# KMO_IO_MV2_8_min.net
KiCad netlist of a schematic drawn in EAGLE
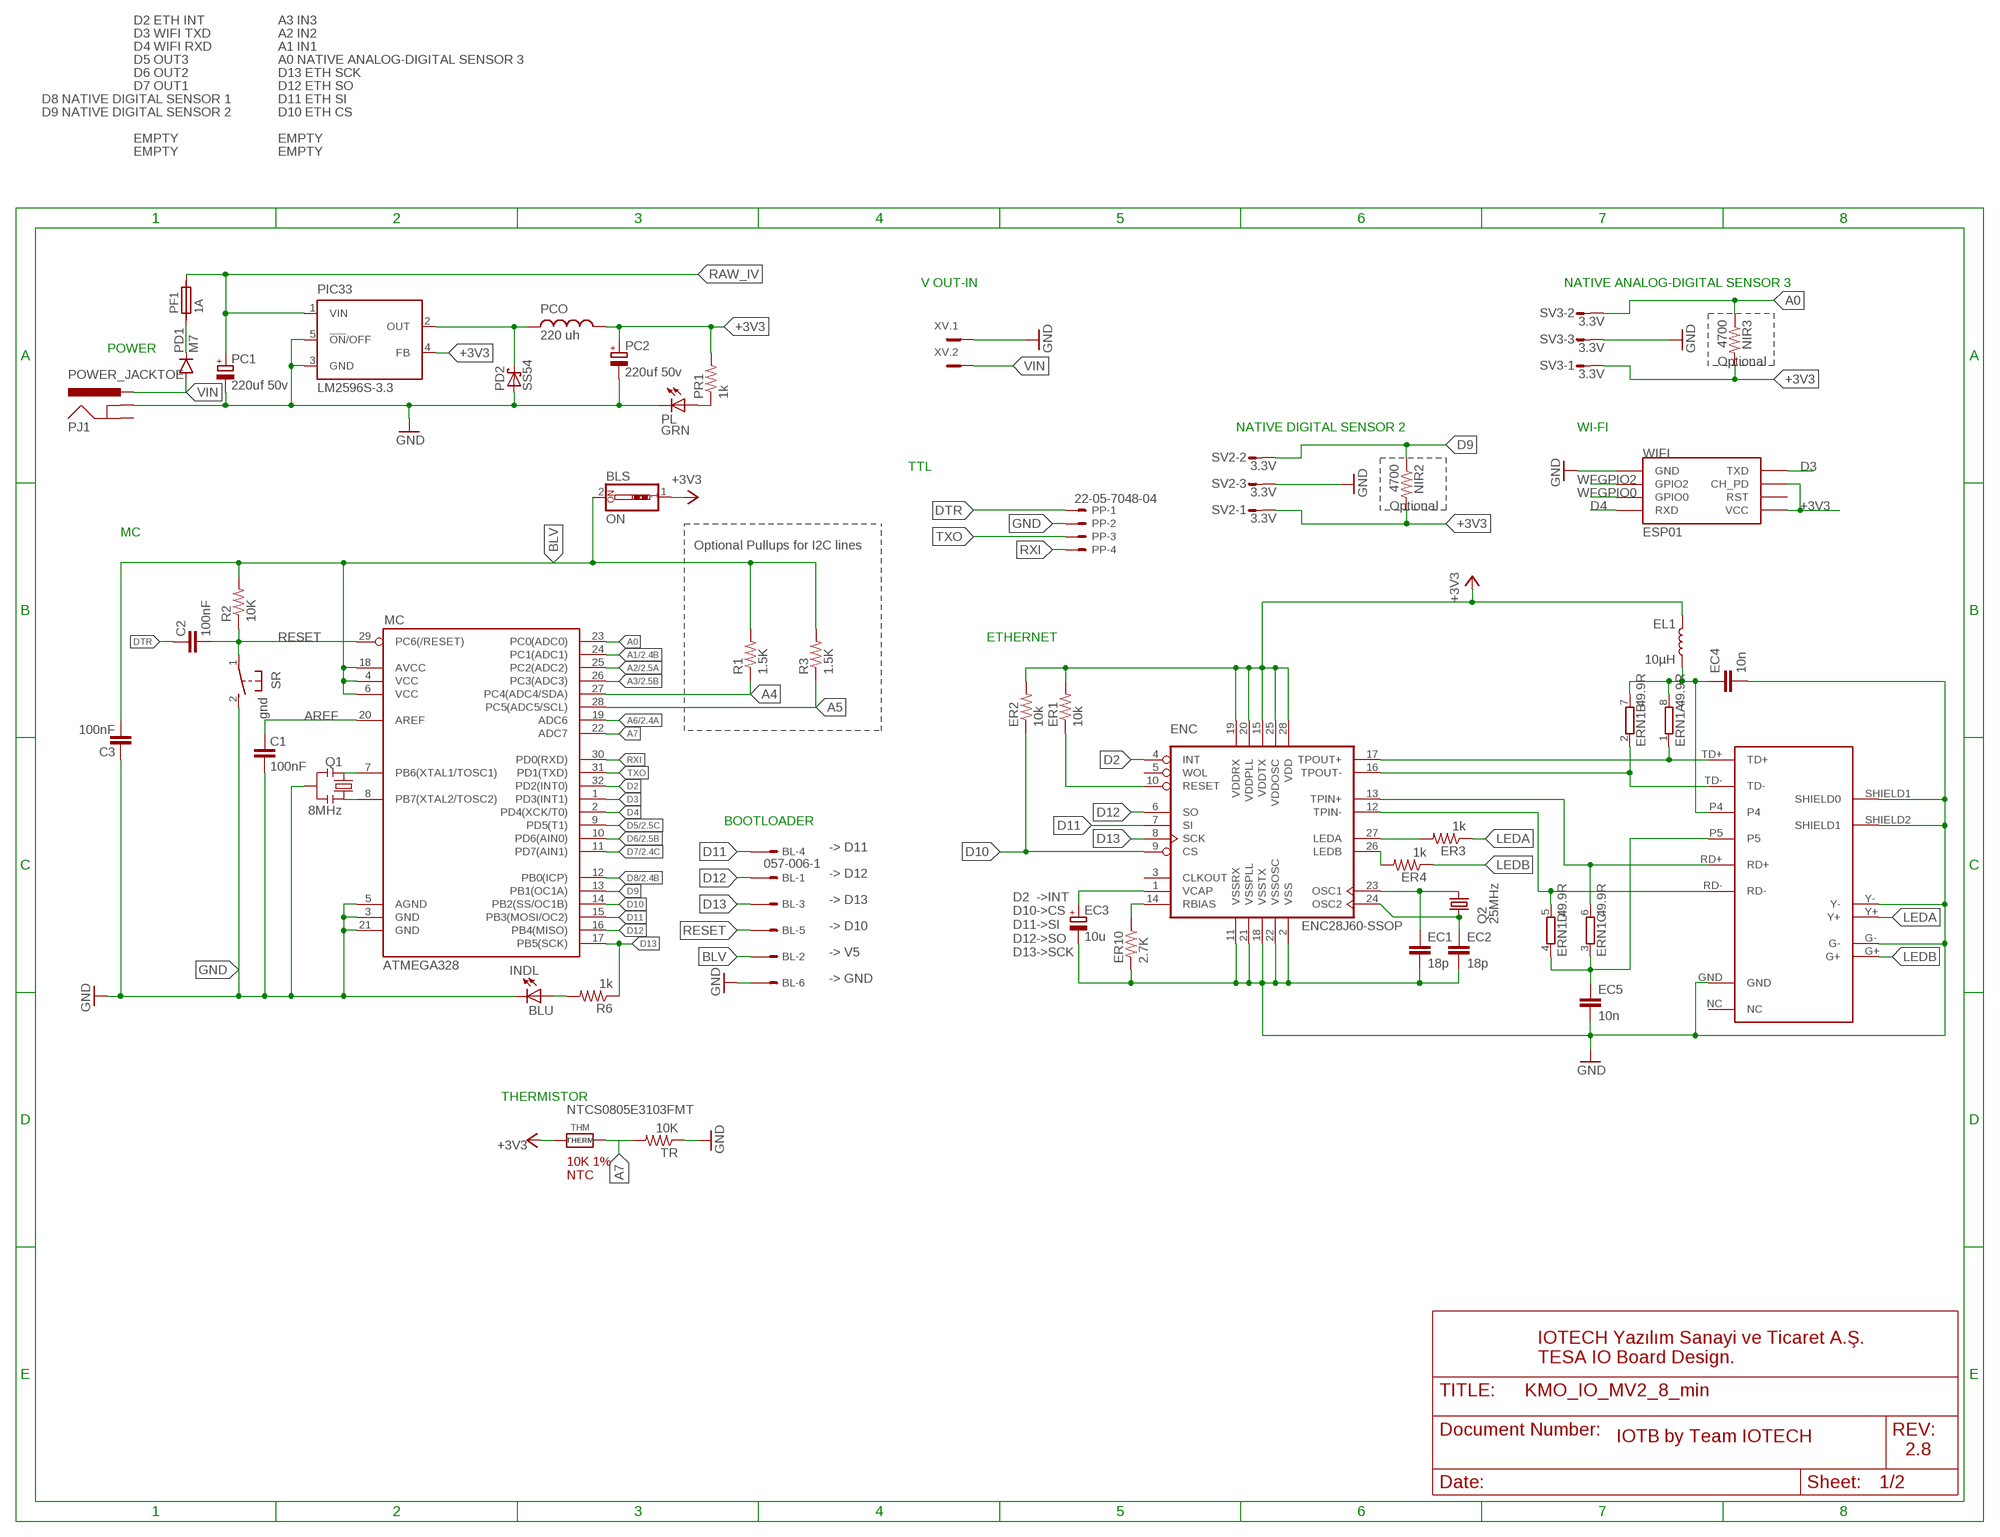
[diagram p0: schematic, sheet 1]
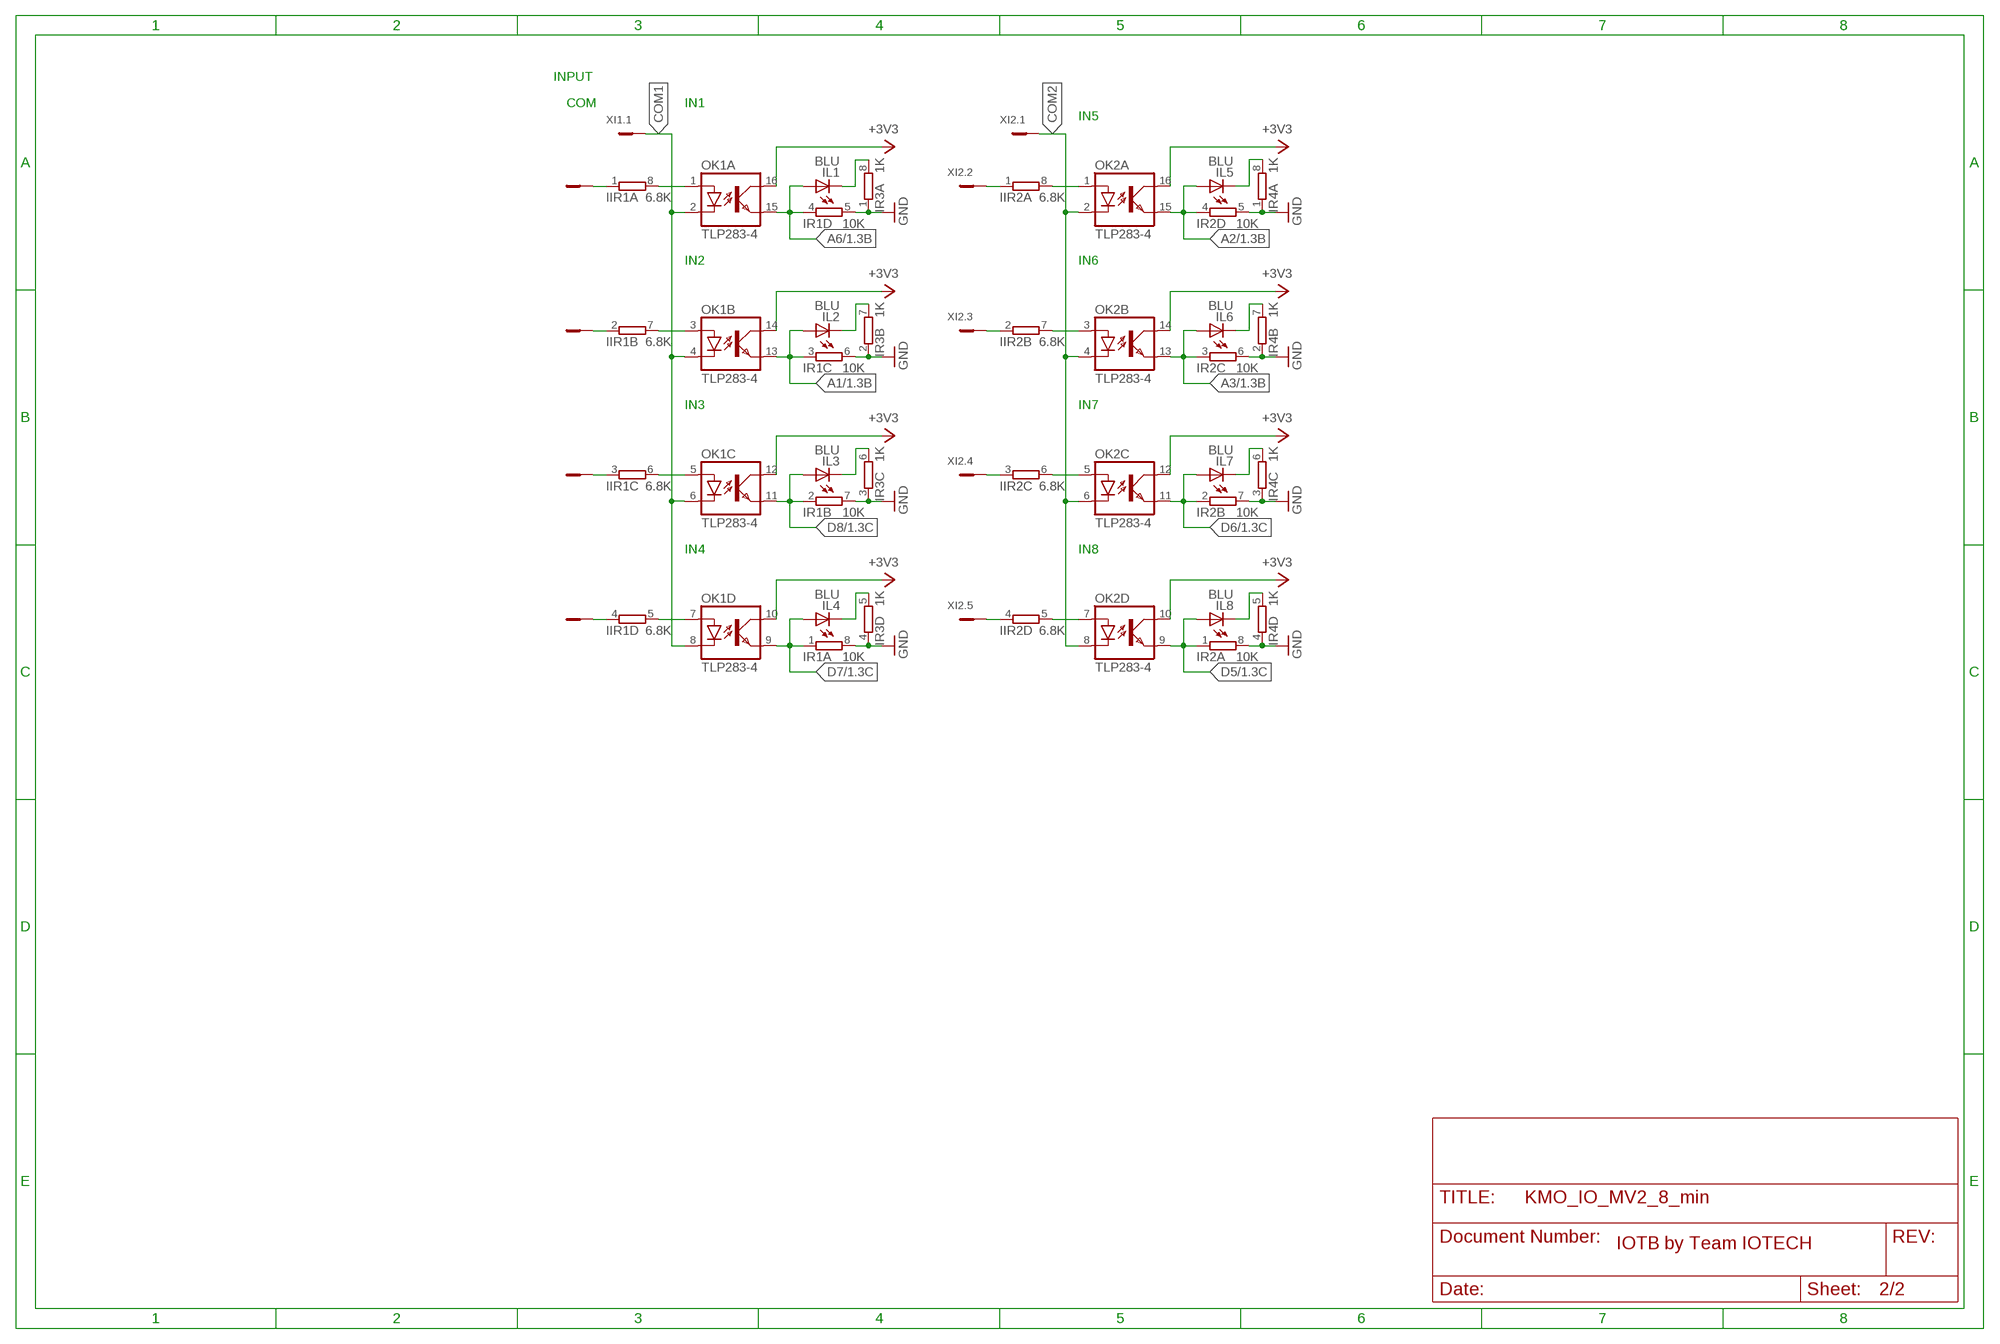
[diagram p1: schematic, sheet 2]

(export (version "E")
  (design (tool "Eeschema 10.0.6"))
  (components
    (comp (ref "IIR1")
      (value "6.8K")
      (footprint "eagle-import:0603-ARV")
      (libsource (lib "eagle-import") (part "4R-N0603-ARV"))
    )
    (comp (ref "IIR2")
      (value "6.8K")
      (footprint "eagle-import:0603-ARV")
      (libsource (lib "eagle-import") (part "4R-N0603-ARV"))
    )
    (comp (ref "IL1")
      (value "BLU")
      (footprint "eagle-import:CHIP-LED0805")
      (libsource (lib "eagle-import") (part "LEDCHIP-LED0805"))
    )
    (comp (ref "IL2")
      (value "BLU")
      (footprint "eagle-import:CHIP-LED0805")
      (libsource (lib "eagle-import") (part "LEDCHIP-LED0805"))
    )
    (comp (ref "IL3")
      (value "BLU")
      (footprint "eagle-import:CHIP-LED0805")
      (libsource (lib "eagle-import") (part "LEDCHIP-LED0805"))
    )
    (comp (ref "IL4")
      (value "BLU")
      (footprint "eagle-import:CHIP-LED0805")
      (libsource (lib "eagle-import") (part "LEDCHIP-LED0805"))
    )
    (comp (ref "IL5")
      (value "BLU")
      (footprint "eagle-import:CHIP-LED0805")
      (libsource (lib "eagle-import") (part "LEDCHIP-LED0805"))
    )
    (comp (ref "IL6")
      (value "BLU")
      (footprint "eagle-import:CHIP-LED0805")
      (libsource (lib "eagle-import") (part "LEDCHIP-LED0805"))
    )
    (comp (ref "IL7")
      (value "BLU")
      (footprint "eagle-import:CHIP-LED0805")
      (libsource (lib "eagle-import") (part "LEDCHIP-LED0805"))
    )
    (comp (ref "IL8")
      (value "BLU")
      (footprint "eagle-import:CHIP-LED0805")
      (libsource (lib "eagle-import") (part "LEDCHIP-LED0805"))
    )
    (comp (ref "IR1")
      (value "10K")
      (footprint "eagle-import:0603-ARV")
      (libsource (lib "eagle-import") (part "4R-N0603-ARV"))
    )
    (comp (ref "IR2")
      (value "10K")
      (footprint "eagle-import:0603-ARV")
      (libsource (lib "eagle-import") (part "4R-N0603-ARV"))
    )
    (comp (ref "IR3")
      (value "1K")
      (footprint "eagle-import:0603-ARV")
      (libsource (lib "eagle-import") (part "4R-N0603-ARV"))
    )
    (comp (ref "IR4")
      (value "1K")
      (footprint "eagle-import:0603-ARV")
      (libsource (lib "eagle-import") (part "4R-N0603-ARV"))
    )
    (comp (ref "OK1")
      (value "TLP283-4")
      (footprint "eagle-import:MINI-FLAT-16")
      (fields (field (name "SPICEPREFIX") "O"))
      (libsource (lib "eagle-import") (part "TLP283-4"))
    )
    (comp (ref "OK2")
      (value "TLP283-4")
      (footprint "eagle-import:MINI-FLAT-16")
      (fields (field (name "SPICEPREFIX") "O"))
      (libsource (lib "eagle-import") (part "TLP283-4"))
    )
    (comp (ref "XI1")
      (value "MC5")
      (footprint "eagle-import:MC5")
      (libsource (lib "eagle-import") (part "MC5"))
    )
    (comp (ref "XI2")
      (value "MC5")
      (footprint "eagle-import:MC5")
      (libsource (lib "eagle-import") (part "MC5"))
    )
    (comp (ref "BL")
      (value "057-006-1")
      (footprint "eagle-import:057-006-1")
      (libsource (lib "eagle-import") (part "057-006-1"))
    )
    (comp (ref "BLS")
      (value "ON")
      (footprint "eagle-import:EDG-01")
      (libsource (lib "eagle-import") (part "SW_DIP-1"))
    )
    (comp (ref "C1")
      (value "100nF")
      (footprint "eagle-import:0805")
      (libsource (lib "eagle-import") (part "CAP0805"))
    )
    (comp (ref "C2")
      (value "100nF")
      (footprint "eagle-import:0805")
      (libsource (lib "eagle-import") (part "CAP0805"))
    )
    (comp (ref "C3")
      (value "100nF")
      (footprint "eagle-import:0805")
      (libsource (lib "eagle-import") (part "CAP0805"))
    )
    (comp (ref "EC1")
      (value "18p")
      (footprint "eagle-import:0805")
      (libsource (lib "eagle-import") (part "CAP0805"))
    )
    (comp (ref "EC2")
      (value "18p")
      (footprint "eagle-import:0805")
      (libsource (lib "eagle-import") (part "CAP0805"))
    )
    (comp (ref "EC3")
      (value "10u")
      (footprint "eagle-import:CT3216")
      (libsource (lib "eagle-import") (part "CPOL-EUCT3216"))
    )
    (comp (ref "EC4")
      (value "10n")
      (footprint "eagle-import:0805")
      (libsource (lib "eagle-import") (part "CAP0805"))
    )
    (comp (ref "EC5")
      (value "10n")
      (footprint "eagle-import:0805")
      (libsource (lib "eagle-import") (part "CAP0805"))
    )
    (comp (ref "EL1")
      (value "10µH")
      (footprint "eagle-import:0805")
      (libsource (lib "eagle-import") (part "INDUCTOR-0805-3.3UH"))
    )
    (comp (ref "ENC")
      (value "ENC28J60-SSOP")
      (footprint "eagle-import:SSOP28")
      (libsource (lib "eagle-import") (part "ENC28J60-SSOP"))
    )
    (comp (ref "ER1")
      (value "10k")
      (footprint "eagle-import:0805")
      (libsource (lib "eagle-import") (part "RESISTOR0805-RES"))
    )
    (comp (ref "ER2")
      (value "10k")
      (footprint "eagle-import:0805")
      (libsource (lib "eagle-import") (part "RESISTOR0805-RES"))
    )
    (comp (ref "ER3")
      (value "1k")
      (footprint "eagle-import:0805")
      (libsource (lib "eagle-import") (part "RESISTOR0805-RES"))
    )
    (comp (ref "ER4")
      (value "1k")
      (footprint "eagle-import:0805")
      (libsource (lib "eagle-import") (part "RESISTOR0805-RES"))
    )
    (comp (ref "ER10")
      (value "2.7K")
      (footprint "eagle-import:0805")
      (libsource (lib "eagle-import") (part "RESISTOR0805-RES"))
    )
    (comp (ref "ERN1")
      (value "49.9R")
      (footprint "eagle-import:0603-ARV")
      (libsource (lib "eagle-import") (part "4R-N0603-ARV"))
    )
    (comp (ref "INDL")
      (value "BLU")
      (footprint "eagle-import:CHIP-LED0805")
      (libsource (lib "eagle-import") (part "LEDCHIP-LED0805"))
    )
    (comp (ref "MC")
      (value "ATMEGA328")
      (footprint "eagle-import:TQFP32-08")
      (libsource (lib "eagle-import") (part "ATMEGA168"))
    )
    (comp (ref "NIR2")
      (value "4700")
      (footprint "eagle-import:0805")
      (libsource (lib "eagle-import") (part "RESISTOR0805-RES"))
    )
    (comp (ref "NIR3")
      (value "4700")
      (footprint "eagle-import:0805")
      (libsource (lib "eagle-import") (part "RESISTOR0805-RES"))
    )
    (comp (ref "PC1")
      (value "220uf 50v")
      (footprint "eagle-import:140CLH-1010")
      (libsource (lib "eagle-import") (part "CPOL-EU140CLH-1010"))
    )
    (comp (ref "PC2")
      (value "220uf 50v")
      (footprint "eagle-import:140CLH-1010")
      (libsource (lib "eagle-import") (part "CPOL-EU140CLH-1010"))
    )
    (comp (ref "PCO")
      (value "220 uh")
      (footprint "eagle-import:MSS1260")
      (libsource (lib "eagle-import") (part "MSS1260"))
    )
    (comp (ref "PD1")
      (value "M7")
      (footprint "eagle-import:SMA-DIODE")
      (libsource (lib "eagle-import") (part "DIODESMA"))
    )
    (comp (ref "PD2")
      (value "SS54")
      (footprint "eagle-import:SMB")
      (libsource (lib "eagle-import") (part "SCHOTTKY-DIODESMD"))
    )
    (comp (ref "PF1")
      (value "1A")
      (footprint "eagle-import:1820")
      (libsource (lib "eagle-import") (part "SIBA194600"))
    )
    (comp (ref "PIC33")
      (value "LM2596S-3.3")
      (footprint "eagle-import:TO263-5")
      (fields
        (field (name "MF") "NATIONAL SEMICONDUCTOR")
        (field (name "MPN") "LM2596S-ADJ/NOPB")
        (field (name "SPICEPREFIX") "X")
      )
      (libsource (lib "eagle-import") (part "LM2596S"))
    )
    (comp (ref "PJ1")
      (value "POWER_JACKTOE")
      (footprint "eagle-import:POWER_JACK_SMD_OVERPASTE_TOE")
      (libsource (lib "eagle-import") (part "POWER_JACKTOE"))
    )
    (comp (ref "PL")
      (value "GRN")
      (footprint "eagle-import:CHIP-LED0805")
      (libsource (lib "eagle-import") (part "LEDCHIP-LED0805"))
    )
    (comp (ref "PP")
      (value "22-05-7048-04")
      (footprint "eagle-import:7395-04")
      (fields (field (name "MF") "MOLEX"))
      (libsource (lib "eagle-import") (part "22-?-0405-7048"))
    )
    (comp (ref "PR1")
      (value "1k")
      (footprint "eagle-import:0805")
      (libsource (lib "eagle-import") (part "RESISTOR0805-RES"))
    )
    (comp (ref "Q1")
      (value "8MHz")
      (footprint "eagle-import:RESONATOR-SMD-1_1")
      (libsource (lib "eagle-import") (part "RESONATOR1{colon}1"))
    )
    (comp (ref "Q2")
      (value "25MHz")
      (footprint "eagle-import:5.0X3.2_2")
      (libsource (lib "eagle-import") (part "KX-9B"))
    )
    (comp (ref "R1")
      (value "1.5K")
      (footprint "eagle-import:0805")
      (libsource (lib "eagle-import") (part "RESISTOR0805-RES"))
    )
    (comp (ref "R2")
      (value "10K")
      (footprint "eagle-import:0805")
      (libsource (lib "eagle-import") (part "RESISTOR0805-RES"))
    )
    (comp (ref "R3")
      (value "1.5K")
      (footprint "eagle-import:0805")
      (libsource (lib "eagle-import") (part "RESISTOR0805-RES"))
    )
    (comp (ref "R6")
      (value "1k")
      (footprint "eagle-import:0805")
      (libsource (lib "eagle-import") (part "RESISTOR0805-RES"))
    )
    (comp (ref "SR")
      (value "gnd")
      (footprint "eagle-import:B3F-31XX")
      (fields (field (name "MPN") "B3F-3100"))
      (libsource (lib "eagle-import") (part "31-XX"))
    )
    (comp (ref "SV2")
      (value "3.3V")
      (footprint "eagle-import:S03P")
      (libsource (lib "eagle-import") (part "S03P"))
    )
    (comp (ref "SV3")
      (value "3.3V")
      (footprint "eagle-import:S03P")
      (libsource (lib "eagle-import") (part "S03P"))
    )
    (comp (ref "THM")
      (value "THERM")
      (footprint "eagle-import:MICROBUILDER_0805_NOTHERMALS")
      (libsource (lib "eagle-import") (part "MICROBUILDER_RESISTOR0805_NOTHERMALS"))
    )
    (comp (ref "TR")
      (value "10K")
      (footprint "eagle-import:0805")
      (libsource (lib "eagle-import") (part "RESISTOR0805-RES"))
    )
    (comp (ref "U$2")
      (value "HR911105A")
      (footprint "eagle-import:RJ45")
      (libsource (lib "eagle-import") (part "HR911105A"))
    )
    (comp (ref "WIFI")
      (value "ESP01")
      (footprint "eagle-import:ESP01")
      (libsource (lib "eagle-import") (part "ESP01"))
    )
    (comp (ref "XV")
      (value "MC2")
      (footprint "eagle-import:MC2")
      (libsource (lib "eagle-import") (part "MC2"))
    )
  )
  (nets
    (net (code "1") (name "+3V3") (class "Default")
      (node (ref "BLS") (pin "1") (pinfunction "1_1") (pintype "passive"))
      (node (ref "EL1") (pin "1") (pinfunction "1_1") (pintype "passive"))
      (node (ref "ENC") (pin "15") (pinfunction "VDDTX_15") (pintype "power_in"))
      (node (ref "ENC") (pin "19") (pinfunction "VDDRX_19") (pintype "power_in"))
      (node (ref "ENC") (pin "20") (pinfunction "VDDPLL_20") (pintype "power_in"))
      (node (ref "ENC") (pin "25") (pinfunction "VDDOSC_25") (pintype "power_in"))
      (node (ref "ENC") (pin "28") (pinfunction "VDD_28") (pintype "power_in"))
      (node (ref "ER1") (pin "2") (pinfunction "2_2") (pintype "passive"))
      (node (ref "ER2") (pin "2") (pinfunction "2_2") (pintype "passive"))
      (node (ref "NIR2") (pin "2") (pinfunction "2_2") (pintype "passive"))
      (node (ref "NIR3") (pin "2") (pinfunction "2_2") (pintype "passive"))
      (node (ref "OK1") (pin "10") (pinfunction "COL_10") (pintype "passive"))
      (node (ref "OK1") (pin "12") (pinfunction "COL_12") (pintype "passive"))
      (node (ref "OK1") (pin "14") (pinfunction "COL_14") (pintype "passive"))
      (node (ref "OK1") (pin "16") (pinfunction "COL_16") (pintype "passive"))
      (node (ref "OK2") (pin "10") (pinfunction "COL_10") (pintype "passive"))
      (node (ref "OK2") (pin "12") (pinfunction "COL_12") (pintype "passive"))
      (node (ref "OK2") (pin "14") (pinfunction "COL_14") (pintype "passive"))
      (node (ref "OK2") (pin "16") (pinfunction "COL_16") (pintype "passive"))
      (node (ref "PC2") (pin "+") (pinfunction "+_+") (pintype "passive"))
      (node (ref "PCO") (pin "P$1") (pinfunction "P$1_P$1") (pintype "passive"))
      (node (ref "PIC33") (pin "4") (pinfunction "FB_4") (pintype "input"))
      (node (ref "PR1") (pin "2") (pinfunction "2_2") (pintype "passive"))
      (node (ref "SV2") (pin "1") (pinfunction "S_1") (pintype "passive"))
      (node (ref "SV3") (pin "1") (pinfunction "S_1") (pintype "passive"))
      (node (ref "THM") (pin "1") (pinfunction "1_1") (pintype "passive"))
      (node (ref "WIFI") (pin "CH_PD") (pinfunction "CH_PD_CH_PD") (pintype "bidirectional"))
      (node (ref "WIFI") (pin "VCC") (pinfunction "VCC_VCC") (pintype "bidirectional"))
    )
    (net (code "2") (name "A0") (class "Default")
      (node (ref "MC") (pin "23") (pinfunction "PC0(ADC0)_23") (pintype "bidirectional"))
      (node (ref "NIR3") (pin "1") (pinfunction "1_1") (pintype "passive"))
      (node (ref "SV3") (pin "2") (pinfunction "S_2") (pintype "passive"))
    )
    (net (code "3") (name "A1") (class "Default")
      (node (ref "IL2") (pin "A") (pinfunction "A_A") (pintype "passive"))
      (node (ref "IR1") (pin "3") (pinfunction "1_3") (pintype "passive"))
      (node (ref "MC") (pin "24") (pinfunction "PC1(ADC1)_24") (pintype "bidirectional"))
      (node (ref "OK1") (pin "13") (pinfunction "EMIT_13") (pintype "passive"))
    )
    (net (code "4") (name "A2") (class "Default")
      (node (ref "IL5") (pin "A") (pinfunction "A_A") (pintype "passive"))
      (node (ref "IR2") (pin "4") (pinfunction "1_4") (pintype "passive"))
      (node (ref "MC") (pin "25") (pinfunction "PC2(ADC2)_25") (pintype "bidirectional"))
      (node (ref "OK2") (pin "15") (pinfunction "EMIT_15") (pintype "passive"))
    )
    (net (code "5") (name "A3") (class "Default")
      (node (ref "IL6") (pin "A") (pinfunction "A_A") (pintype "passive"))
      (node (ref "IR2") (pin "3") (pinfunction "1_3") (pintype "passive"))
      (node (ref "MC") (pin "26") (pinfunction "PC3(ADC3)_26") (pintype "bidirectional"))
      (node (ref "OK2") (pin "13") (pinfunction "EMIT_13") (pintype "passive"))
    )
    (net (code "6") (name "A4") (class "Default")
      (node (ref "MC") (pin "27") (pinfunction "PC4(ADC4/SDA)_27") (pintype "bidirectional"))
      (node (ref "R1") (pin "1") (pinfunction "1_1") (pintype "passive"))
    )
    (net (code "7") (name "A5") (class "Default")
      (node (ref "MC") (pin "28") (pinfunction "PC5(ADC5/SCL)_28") (pintype "bidirectional"))
      (node (ref "R3") (pin "1") (pinfunction "1_1") (pintype "passive"))
    )
    (net (code "8") (name "A6") (class "Default")
      (node (ref "IL1") (pin "A") (pinfunction "A_A") (pintype "passive"))
      (node (ref "IR1") (pin "4") (pinfunction "1_4") (pintype "passive"))
      (node (ref "MC") (pin "19") (pinfunction "ADC6_19") (pintype "bidirectional"))
      (node (ref "OK1") (pin "15") (pinfunction "EMIT_15") (pintype "passive"))
    )
    (net (code "9") (name "A7") (class "Default")
      (node (ref "MC") (pin "22") (pinfunction "ADC7_22") (pintype "bidirectional"))
      (node (ref "THM") (pin "2") (pinfunction "2_2") (pintype "passive"))
      (node (ref "TR") (pin "2") (pinfunction "2_2") (pintype "passive"))
    )
    (net (code "10") (name "AREF") (class "Default")
      (node (ref "C1") (pin "2") (pinfunction "2_2") (pintype "passive"))
      (node (ref "MC") (pin "20") (pinfunction "AREF_20") (pintype "bidirectional"))
    )
    (net (code "11") (name "BLV") (class "Default")
      (node (ref "BL") (pin "2") (pinfunction "S_2") (pintype "passive"))
      (node (ref "BLS") (pin "2") (pinfunction "2_2") (pintype "passive"))
      (node (ref "C3") (pin "1") (pinfunction "1_1") (pintype "passive"))
      (node (ref "MC") (pin "18") (pinfunction "AVCC_18") (pintype "bidirectional"))
      (node (ref "MC") (pin "4") (pinfunction "VCC_4") (pintype "bidirectional"))
      (node (ref "MC") (pin "6") (pinfunction "VCC_6") (pintype "bidirectional"))
      (node (ref "R1") (pin "2") (pinfunction "2_2") (pintype "passive"))
      (node (ref "R2") (pin "2") (pinfunction "2_2") (pintype "passive"))
      (node (ref "R3") (pin "2") (pinfunction "2_2") (pintype "passive"))
    )
    (net (code "12") (name "COM1") (class "Default")
      (node (ref "OK1") (pin "2") (pinfunction "C_2") (pintype "passive"))
      (node (ref "OK1") (pin "4") (pinfunction "C_4") (pintype "passive"))
      (node (ref "OK1") (pin "6") (pinfunction "C_6") (pintype "passive"))
      (node (ref "OK1") (pin "8") (pinfunction "C_8") (pintype "passive"))
      (node (ref "XI1") (pin "1") (pinfunction "SK_1") (pintype "passive"))
    )
    (net (code "13") (name "COM2") (class "Default")
      (node (ref "OK2") (pin "2") (pinfunction "C_2") (pintype "passive"))
      (node (ref "OK2") (pin "4") (pinfunction "C_4") (pintype "passive"))
      (node (ref "OK2") (pin "6") (pinfunction "C_6") (pintype "passive"))
      (node (ref "OK2") (pin "8") (pinfunction "C_8") (pintype "passive"))
      (node (ref "XI2") (pin "1") (pinfunction "SK_1") (pintype "passive"))
    )
    (net (code "14") (name "D2") (class "Default")
      (node (ref "ENC") (pin "4") (pinfunction "INT_4") (pintype "output"))
      (node (ref "MC") (pin "32") (pinfunction "PD2(INT0)_32") (pintype "bidirectional"))
    )
    (net (code "15") (name "D3") (class "Default")
      (node (ref "MC") (pin "1") (pinfunction "PD3(INT1)_1") (pintype "bidirectional"))
      (node (ref "WIFI") (pin "TX") (pinfunction "TXD_TX") (pintype "bidirectional"))
    )
    (net (code "16") (name "D4") (class "Default")
      (node (ref "MC") (pin "2") (pinfunction "PD4(XCK/T0)_2") (pintype "bidirectional"))
      (node (ref "WIFI") (pin "RX") (pinfunction "RXD_RX") (pintype "bidirectional"))
    )
    (net (code "17") (name "D5") (class "Default")
      (node (ref "IL8") (pin "A") (pinfunction "A_A") (pintype "passive"))
      (node (ref "IR2") (pin "1") (pinfunction "1_1") (pintype "passive"))
      (node (ref "MC") (pin "9") (pinfunction "PD5(T1)_9") (pintype "bidirectional"))
      (node (ref "OK2") (pin "9") (pinfunction "EMIT_9") (pintype "passive"))
    )
    (net (code "18") (name "D6") (class "Default")
      (node (ref "IL7") (pin "A") (pinfunction "A_A") (pintype "passive"))
      (node (ref "IR2") (pin "2") (pinfunction "1_2") (pintype "passive"))
      (node (ref "MC") (pin "10") (pinfunction "PD6(AIN0)_10") (pintype "bidirectional"))
      (node (ref "OK2") (pin "11") (pinfunction "EMIT_11") (pintype "passive"))
    )
    (net (code "19") (name "D7") (class "Default")
      (node (ref "IL4") (pin "A") (pinfunction "A_A") (pintype "passive"))
      (node (ref "IR1") (pin "1") (pinfunction "1_1") (pintype "passive"))
      (node (ref "MC") (pin "11") (pinfunction "PD7(AIN1)_11") (pintype "bidirectional"))
      (node (ref "OK1") (pin "9") (pinfunction "EMIT_9") (pintype "passive"))
    )
    (net (code "20") (name "D8") (class "Default")
      (node (ref "IL3") (pin "A") (pinfunction "A_A") (pintype "passive"))
      (node (ref "IR1") (pin "2") (pinfunction "1_2") (pintype "passive"))
      (node (ref "MC") (pin "12") (pinfunction "PB0(ICP)_12") (pintype "bidirectional"))
      (node (ref "OK1") (pin "11") (pinfunction "EMIT_11") (pintype "passive"))
    )
    (net (code "21") (name "D9") (class "Default")
      (node (ref "MC") (pin "13") (pinfunction "PB1(OC1A)_13") (pintype "bidirectional"))
      (node (ref "NIR2") (pin "1") (pinfunction "1_1") (pintype "passive"))
      (node (ref "SV2") (pin "2") (pinfunction "S_2") (pintype "passive"))
    )
    (net (code "22") (name "D10") (class "Default")
      (node (ref "ENC") (pin "9") (pinfunction "CS_9") (pintype "input"))
      (node (ref "ER2") (pin "1") (pinfunction "1_1") (pintype "passive"))
      (node (ref "MC") (pin "14") (pinfunction "PB2(SS/OC1B)_14") (pintype "bidirectional"))
    )
    (net (code "23") (name "D11") (class "Default")
      (node (ref "BL") (pin "4") (pinfunction "S_4") (pintype "passive"))
      (node (ref "ENC") (pin "7") (pinfunction "SI_7") (pintype "input"))
      (node (ref "MC") (pin "15") (pinfunction "PB3(MOSI/OC2)_15") (pintype "bidirectional"))
    )
    (net (code "24") (name "D12") (class "Default")
      (node (ref "BL") (pin "1") (pinfunction "S_1") (pintype "passive"))
      (node (ref "ENC") (pin "6") (pinfunction "SO_6") (pintype "output"))
      (node (ref "MC") (pin "16") (pinfunction "PB4(MISO)_16") (pintype "bidirectional"))
    )
    (net (code "25") (name "D13") (class "Default")
      (node (ref "BL") (pin "3") (pinfunction "S_3") (pintype "passive"))
      (node (ref "ENC") (pin "8") (pinfunction "SCK_8") (pintype "input"))
      (node (ref "MC") (pin "17") (pinfunction "PB5(SCK)_17") (pintype "bidirectional"))
      (node (ref "R6") (pin "1") (pinfunction "1_1") (pintype "passive"))
    )
    (net (code "26") (name "DTR") (class "Default")
      (node (ref "C2") (pin "2") (pinfunction "2_2") (pintype "passive"))
      (node (ref "PP") (pin "1") (pinfunction "S_1") (pintype "passive"))
    )
    (net (code "27") (name "GND") (class "Default")
      (node (ref "BL") (pin "6") (pinfunction "S_6") (pintype "passive"))
      (node (ref "C1") (pin "1") (pinfunction "1_1") (pintype "passive"))
      (node (ref "C3") (pin "2") (pinfunction "2_2") (pintype "passive"))
      (node (ref "EC1") (pin "2") (pinfunction "2_2") (pintype "passive"))
      (node (ref "EC2") (pin "2") (pinfunction "2_2") (pintype "passive"))
      (node (ref "EC3") (pin "-") (pinfunction "-_-") (pintype "passive"))
      (node (ref "EC4") (pin "2") (pinfunction "2_2") (pintype "passive"))
      (node (ref "EC5") (pin "2") (pinfunction "2_2") (pintype "passive"))
      (node (ref "ENC") (pin "11") (pinfunction "VSSRX_11") (pintype "power_in"))
      (node (ref "ENC") (pin "18") (pinfunction "VSSTX_18") (pintype "power_in"))
      (node (ref "ENC") (pin "2") (pinfunction "VSS_2") (pintype "power_in"))
      (node (ref "ENC") (pin "21") (pinfunction "VSSPLL_21") (pintype "power_in"))
      (node (ref "ENC") (pin "22") (pinfunction "VSSOSC_22") (pintype "power_in"))
      (node (ref "ER10") (pin "2") (pinfunction "2_2") (pintype "passive"))
      (node (ref "INDL") (pin "C") (pinfunction "C_C") (pintype "passive"))
      (node (ref "IR1") (pin "5") (pinfunction "2_5") (pintype "passive"))
      (node (ref "IR1") (pin "6") (pinfunction "2_6") (pintype "passive"))
      (node (ref "IR1") (pin "7") (pinfunction "2_7") (pintype "passive"))
      (node (ref "IR1") (pin "8") (pinfunction "2_8") (pintype "passive"))
      (node (ref "IR2") (pin "5") (pinfunction "2_5") (pintype "passive"))
      (node (ref "IR2") (pin "6") (pinfunction "2_6") (pintype "passive"))
      (node (ref "IR2") (pin "7") (pinfunction "2_7") (pintype "passive"))
      (node (ref "IR2") (pin "8") (pinfunction "2_8") (pintype "passive"))
      (node (ref "IR3") (pin "1") (pinfunction "1_1") (pintype "passive"))
      (node (ref "IR3") (pin "2") (pinfunction "1_2") (pintype "passive"))
      (node (ref "IR3") (pin "3") (pinfunction "1_3") (pintype "passive"))
      (node (ref "IR3") (pin "4") (pinfunction "1_4") (pintype "passive"))
      (node (ref "IR4") (pin "1") (pinfunction "1_1") (pintype "passive"))
      (node (ref "IR4") (pin "2") (pinfunction "1_2") (pintype "passive"))
      (node (ref "IR4") (pin "3") (pinfunction "1_3") (pintype "passive"))
      (node (ref "IR4") (pin "4") (pinfunction "1_4") (pintype "passive"))
      (node (ref "MC") (pin "21") (pinfunction "GND_21") (pintype "bidirectional"))
      (node (ref "MC") (pin "3") (pinfunction "GND_3") (pintype "bidirectional"))
      (node (ref "MC") (pin "5") (pinfunction "AGND_5") (pintype "bidirectional"))
      (node (ref "PC1") (pin "-") (pinfunction "-_-") (pintype "passive"))
      (node (ref "PC2") (pin "-") (pinfunction "-_-") (pintype "passive"))
      (node (ref "PD2") (pin "A") (pinfunction "A_A") (pintype "passive"))
      (node (ref "PIC33") (pin "3") (pinfunction "GND_3") (pintype "power_in"))
      (node (ref "PIC33") (pin "5") (pinfunction "~{ON}/OFF_5") (pintype "input"))
      (node (ref "PJ1") (pin "GND") (pinfunction "GNDBREAK_GND") (pintype "bidirectional"))
      (node (ref "PL") (pin "C") (pinfunction "C_C") (pintype "passive"))
      (node (ref "PP") (pin "2") (pinfunction "S_2") (pintype "passive"))
      (node (ref "Q1") (pin "2") (pinfunction "2_2") (pintype "passive"))
      (node (ref "SR") (pin "2") (pinfunction "S_2") (pintype "passive"))
      (node (ref "SV2") (pin "3") (pinfunction "S_3") (pintype "passive"))
      (node (ref "SV3") (pin "3") (pinfunction "S_3") (pintype "passive"))
      (node (ref "TR") (pin "1") (pinfunction "1_1") (pintype "passive"))
      (node (ref "U$2") (pin "G-") (pinfunction "G-_G-") (pintype "bidirectional"))
      (node (ref "U$2") (pin "GND") (pinfunction "GND_GND") (pintype "bidirectional"))
      (node (ref "U$2") (pin "SHIELD1") (pinfunction "SHIELD0_SHIELD1") (pintype "bidirectional"))
      (node (ref "U$2") (pin "SHIELD2") (pinfunction "SHIELD1_SHIELD2") (pintype "bidirectional"))
      (node (ref "U$2") (pin "Y-") (pinfunction "Y-_Y-") (pintype "bidirectional"))
      (node (ref "WIFI") (pin "GND") (pinfunction "GND_GND") (pintype "bidirectional"))
      (node (ref "XV") (pin "1") (pinfunction "SK_1") (pintype "passive"))
    )
    (net (code "28") (name "LEDA") (class "Default")
      (node (ref "ER3") (pin "1") (pinfunction "1_1") (pintype "passive"))
      (node (ref "U$2") (pin "Y+") (pinfunction "Y+_Y+") (pintype "bidirectional"))
    )
    (net (code "29") (name "LEDB") (class "Default")
      (node (ref "ER4") (pin "1") (pinfunction "1_1") (pintype "passive"))
      (node (ref "U$2") (pin "G+") (pinfunction "G+_G+") (pintype "bidirectional"))
    )
    (net (code "30") (name "Net-(ENC-LEDA)") (class "Default")
      (node (ref "ENC") (pin "27") (pinfunction "LEDA_27") (pintype "output"))
      (node (ref "ER3") (pin "2") (pinfunction "2_2") (pintype "passive"))
    )
    (net (code "31") (name "Net-(ENC-LEDB)") (class "Default")
      (node (ref "ENC") (pin "26") (pinfunction "LEDB_26") (pintype "output"))
      (node (ref "ER4") (pin "2") (pinfunction "2_2") (pintype "passive"))
    )
    (net (code "32") (name "Net-(ENC-OSC1)") (class "Default")
      (node (ref "EC1") (pin "1") (pinfunction "1_1") (pintype "passive"))
      (node (ref "ENC") (pin "23") (pinfunction "OSC1_23") (pintype "input"))
      (node (ref "Q2") (pin "2") (pinfunction "2_2") (pintype "passive"))
    )
    (net (code "33") (name "Net-(ENC-OSC2)") (class "Default")
      (node (ref "EC2") (pin "1") (pinfunction "1_1") (pintype "passive"))
      (node (ref "ENC") (pin "24") (pinfunction "OSC2_24") (pintype "output"))
      (node (ref "Q2") (pin "1") (pinfunction "1_1") (pintype "passive"))
    )
    (net (code "34") (name "Net-(ENC-RBIAS)") (class "Default")
      (node (ref "ENC") (pin "14") (pinfunction "RBIAS_14") (pintype "passive"))
      (node (ref "ER10") (pin "1") (pinfunction "1_1") (pintype "passive"))
    )
    (net (code "35") (name "Net-(ENC-RESET)") (class "Default")
      (node (ref "ENC") (pin "10") (pinfunction "RESET_10") (pintype "input"))
      (node (ref "ER1") (pin "1") (pinfunction "1_1") (pintype "passive"))
    )
    (net (code "36") (name "Net-(ENC-TPIN+)") (class "Default")
      (node (ref "ENC") (pin "13") (pinfunction "TPIN+_13") (pintype "input"))
      (node (ref "ERN1") (pin "6") (pinfunction "2_6") (pintype "passive"))
      (node (ref "U$2") (pin "RD+") (pinfunction "RD+_RD+") (pintype "bidirectional"))
    )
    (net (code "37") (name "Net-(ENC-TPIN-)") (class "Default")
      (node (ref "ENC") (pin "12") (pinfunction "TPIN-_12") (pintype "input"))
      (node (ref "ERN1") (pin "5") (pinfunction "2_5") (pintype "passive"))
      (node (ref "U$2") (pin "RD-") (pinfunction "RD-_RD-") (pintype "bidirectional"))
    )
    (net (code "38") (name "Net-(ENC-TPOUT+)") (class "Default")
      (node (ref "ENC") (pin "17") (pinfunction "TPOUT+_17") (pintype "output"))
      (node (ref "ERN1") (pin "1") (pinfunction "1_1") (pintype "passive"))
      (node (ref "U$2") (pin "TD+") (pinfunction "TD+_TD+") (pintype "bidirectional"))
    )
    (net (code "39") (name "Net-(ENC-TPOUT-)") (class "Default")
      (node (ref "ENC") (pin "16") (pinfunction "TPOUT-_16") (pintype "output"))
      (node (ref "ERN1") (pin "2") (pinfunction "1_2") (pintype "passive"))
      (node (ref "U$2") (pin "TD-") (pinfunction "TD-_TD-") (pintype "bidirectional"))
    )
    (net (code "40") (name "Net-(ENC-VCAP)") (class "Default")
      (node (ref "EC3") (pin "+") (pinfunction "+_+") (pintype "passive"))
      (node (ref "ENC") (pin "1") (pinfunction "VCAP_1") (pintype "power_in"))
    )
    (net (code "41") (name "Net-(ERN1A-2)") (class "Default")
      (node (ref "EC4") (pin "1") (pinfunction "1_1") (pintype "passive"))
      (node (ref "EL1") (pin "2") (pinfunction "2_2") (pintype "passive"))
      (node (ref "ERN1") (pin "7") (pinfunction "2_7") (pintype "passive"))
      (node (ref "ERN1") (pin "8") (pinfunction "2_8") (pintype "passive"))
      (node (ref "U$2") (pin "P4") (pinfunction "P4_P4") (pintype "bidirectional"))
    )
    (net (code "42") (name "Net-(ERN1C-1)") (class "Default")
      (node (ref "EC5") (pin "1") (pinfunction "1_1") (pintype "passive"))
      (node (ref "ERN1") (pin "3") (pinfunction "1_3") (pintype "passive"))
      (node (ref "ERN1") (pin "4") (pinfunction "1_4") (pintype "passive"))
      (node (ref "U$2") (pin "P5") (pinfunction "P5_P5") (pintype "bidirectional"))
    )
    (net (code "43") (name "Net-(IIR1A-2)") (class "Default")
      (node (ref "IIR1") (pin "8") (pinfunction "2_8") (pintype "passive"))
      (node (ref "OK1") (pin "1") (pinfunction "A_1") (pintype "passive"))
    )
    (net (code "44") (name "Net-(IIR1B-1)") (class "Default")
      (node (ref "IIR1") (pin "2") (pinfunction "1_2") (pintype "passive"))
      (node (ref "XI1") (pin "3") (pinfunction "SK_3") (pintype "passive"))
    )
    (net (code "45") (name "Net-(IIR1B-2)") (class "Default")
      (node (ref "IIR1") (pin "7") (pinfunction "2_7") (pintype "passive"))
      (node (ref "OK1") (pin "3") (pinfunction "A_3") (pintype "passive"))
    )
    (net (code "46") (name "Net-(IIR1C-1)") (class "Default")
      (node (ref "IIR1") (pin "3") (pinfunction "1_3") (pintype "passive"))
      (node (ref "XI1") (pin "4") (pinfunction "SK_4") (pintype "passive"))
    )
    (net (code "47") (name "Net-(IIR1C-2)") (class "Default")
      (node (ref "IIR1") (pin "6") (pinfunction "2_6") (pintype "passive"))
      (node (ref "OK1") (pin "5") (pinfunction "A_5") (pintype "passive"))
    )
    (net (code "48") (name "Net-(IIR1D-1)") (class "Default")
      (node (ref "IIR1") (pin "4") (pinfunction "1_4") (pintype "passive"))
      (node (ref "XI1") (pin "5") (pinfunction "SK_5") (pintype "passive"))
    )
    (net (code "49") (name "Net-(IIR1D-2)") (class "Default")
      (node (ref "IIR1") (pin "5") (pinfunction "2_5") (pintype "passive"))
      (node (ref "OK1") (pin "7") (pinfunction "A_7") (pintype "passive"))
    )
    (net (code "50") (name "Net-(IIR2A-2)") (class "Default")
      (node (ref "IIR2") (pin "8") (pinfunction "2_8") (pintype "passive"))
      (node (ref "OK2") (pin "1") (pinfunction "A_1") (pintype "passive"))
    )
    (net (code "51") (name "Net-(IIR2B-1)") (class "Default")
      (node (ref "IIR2") (pin "2") (pinfunction "1_2") (pintype "passive"))
      (node (ref "XI2") (pin "3") (pinfunction "SK_3") (pintype "passive"))
    )
    (net (code "52") (name "Net-(IIR2B-2)") (class "Default")
      (node (ref "IIR2") (pin "7") (pinfunction "2_7") (pintype "passive"))
      (node (ref "OK2") (pin "3") (pinfunction "A_3") (pintype "passive"))
    )
    (net (code "53") (name "Net-(IIR2C-1)") (class "Default")
      (node (ref "IIR2") (pin "3") (pinfunction "1_3") (pintype "passive"))
      (node (ref "XI2") (pin "4") (pinfunction "SK_4") (pintype "passive"))
    )
    (net (code "54") (name "Net-(IIR2C-2)") (class "Default")
      (node (ref "IIR2") (pin "6") (pinfunction "2_6") (pintype "passive"))
      (node (ref "OK2") (pin "5") (pinfunction "A_5") (pintype "passive"))
    )
    (net (code "55") (name "Net-(IIR2D-1)") (class "Default")
      (node (ref "IIR2") (pin "4") (pinfunction "1_4") (pintype "passive"))
      (node (ref "XI2") (pin "5") (pinfunction "SK_5") (pintype "passive"))
    )
    (net (code "56") (name "Net-(IIR2D-2)") (class "Default")
      (node (ref "IIR2") (pin "5") (pinfunction "2_5") (pintype "passive"))
      (node (ref "OK2") (pin "7") (pinfunction "A_7") (pintype "passive"))
    )
    (net (code "57") (name "Net-(INDL-PadA)") (class "Default")
      (node (ref "INDL") (pin "A") (pinfunction "A_A") (pintype "passive"))
      (node (ref "R6") (pin "2") (pinfunction "2_2") (pintype "passive"))
    )
    (net (code "58") (name "Net-(IR3A-2)") (class "Default")
      (node (ref "IL1") (pin "C") (pinfunction "C_C") (pintype "passive"))
      (node (ref "IR3") (pin "8") (pinfunction "2_8") (pintype "passive"))
    )
    (net (code "59") (name "Net-(IR3B-2)") (class "Default")
      (node (ref "IL2") (pin "C") (pinfunction "C_C") (pintype "passive"))
      (node (ref "IR3") (pin "7") (pinfunction "2_7") (pintype "passive"))
    )
    (net (code "60") (name "Net-(IR3C-2)") (class "Default")
      (node (ref "IL3") (pin "C") (pinfunction "C_C") (pintype "passive"))
      (node (ref "IR3") (pin "6") (pinfunction "2_6") (pintype "passive"))
    )
    (net (code "61") (name "Net-(IR3D-2)") (class "Default")
      (node (ref "IL4") (pin "C") (pinfunction "C_C") (pintype "passive"))
      (node (ref "IR3") (pin "5") (pinfunction "2_5") (pintype "passive"))
    )
    (net (code "62") (name "Net-(IR4A-2)") (class "Default")
      (node (ref "IL5") (pin "C") (pinfunction "C_C") (pintype "passive"))
      (node (ref "IR4") (pin "8") (pinfunction "2_8") (pintype "passive"))
    )
    (net (code "63") (name "Net-(IR4B-2)") (class "Default")
      (node (ref "IL6") (pin "C") (pinfunction "C_C") (pintype "passive"))
      (node (ref "IR4") (pin "7") (pinfunction "2_7") (pintype "passive"))
    )
    (net (code "64") (name "Net-(IR4C-2)") (class "Default")
      (node (ref "IL7") (pin "C") (pinfunction "C_C") (pintype "passive"))
      (node (ref "IR4") (pin "6") (pinfunction "2_6") (pintype "passive"))
    )
    (net (code "65") (name "Net-(IR4D-2)") (class "Default")
      (node (ref "IL8") (pin "C") (pinfunction "C_C") (pintype "passive"))
      (node (ref "IR4") (pin "5") (pinfunction "2_5") (pintype "passive"))
    )
    (net (code "66") (name "Net-(MC-PB6(XTAL1{slash}TOSC1))") (class "Default")
      (node (ref "MC") (pin "7") (pinfunction "PB6(XTAL1/TOSC1)_7") (pintype "bidirectional"))
      (node (ref "Q1") (pin "1") (pinfunction "1_1") (pintype "passive"))
    )
    (net (code "67") (name "Net-(MC-PB7(XTAL2{slash}TOSC2))") (class "Default")
      (node (ref "MC") (pin "8") (pinfunction "PB7(XTAL2/TOSC2)_8") (pintype "bidirectional"))
      (node (ref "Q1") (pin "3") (pinfunction "3_3") (pintype "passive"))
    )
    (net (code "68") (name "Net-(PD1-PadC)") (class "Default")
      (node (ref "PD1") (pin "C") (pinfunction "C_C") (pintype "passive"))
      (node (ref "PF1") (pin "1") (pinfunction "1_1") (pintype "passive"))
    )
    (net (code "69") (name "Net-(PIC33-OUT)") (class "Default")
      (node (ref "PCO") (pin "P$2") (pinfunction "P$2_P$2") (pintype "passive"))
      (node (ref "PD2") (pin "C") (pinfunction "C_C") (pintype "passive"))
      (node (ref "PIC33") (pin "2") (pinfunction "OUT_2") (pintype "output"))
    )
    (net (code "70") (name "Net-(PL-PadA)") (class "Default")
      (node (ref "PL") (pin "A") (pinfunction "A_A") (pintype "passive"))
      (node (ref "PR1") (pin "1") (pinfunction "1_1") (pintype "passive"))
    )
    (net (code "71") (name "Net-(XI1B-SK)") (class "Default")
      (node (ref "IIR1") (pin "1") (pinfunction "1_1") (pintype "passive"))
      (node (ref "XI1") (pin "2") (pinfunction "SK_2") (pintype "passive"))
    )
    (net (code "72") (name "Net-(XI2B-SK)") (class "Default")
      (node (ref "IIR2") (pin "1") (pinfunction "1_1") (pintype "passive"))
      (node (ref "XI2") (pin "2") (pinfunction "SK_2") (pintype "passive"))
    )
    (net (code "73") (name "RAW_IV") (class "Default")
      (node (ref "PC1") (pin "+") (pinfunction "+_+") (pintype "passive"))
      (node (ref "PF1") (pin "2") (pinfunction "2_2") (pintype "passive"))
      (node (ref "PIC33") (pin "1") (pinfunction "VIN_1") (pintype "input"))
    )
    (net (code "74") (name "RESET") (class "Default")
      (node (ref "BL") (pin "5") (pinfunction "S_5") (pintype "passive"))
      (node (ref "C2") (pin "1") (pinfunction "1_1") (pintype "passive"))
      (node (ref "MC") (pin "29") (pinfunction "PC6(/RESET)_29") (pintype "bidirectional"))
      (node (ref "R2") (pin "1") (pinfunction "1_1") (pintype "passive"))
      (node (ref "SR") (pin "1") (pinfunction "P_1") (pintype "passive"))
    )
    (net (code "75") (name "RXI") (class "Default")
      (node (ref "MC") (pin "30") (pinfunction "PD0(RXD)_30") (pintype "bidirectional"))
      (node (ref "PP") (pin "4") (pinfunction "S_4") (pintype "passive"))
    )
    (net (code "76") (name "TXO") (class "Default")
      (node (ref "MC") (pin "31") (pinfunction "PD1(TXD)_31") (pintype "bidirectional"))
      (node (ref "PP") (pin "3") (pinfunction "S_3") (pintype "passive"))
    )
    (net (code "77") (name "VIN") (class "Default")
      (node (ref "PD1") (pin "A") (pinfunction "A_A") (pintype "passive"))
      (node (ref "PJ1") (pin "VIN0") (pinfunction "PWR_VIN0") (pintype "bidirectional"))
      (node (ref "XV") (pin "2") (pinfunction "SK_2") (pintype "passive"))
    )
    (net (code "78") (name "WFGPIO0") (class "Default")
      (node (ref "WIFI") (pin "GPIO0") (pinfunction "GPIO0_GPIO0") (pintype "bidirectional"))
    )
    (net (code "79") (name "WFGPIO2") (class "Default")
      (node (ref "WIFI") (pin "GPIO2") (pinfunction "GPIO2_GPIO2") (pintype "bidirectional"))
    )
    (net (code "80") (name "unconnected-(ENC-CLKOUT-Pad3)") (class "Default")
      (node (ref "ENC") (pin "3") (pinfunction "CLKOUT_3") (pintype "output"))
    )
    (net (code "81") (name "unconnected-(ENC-WOL-Pad5)") (class "Default")
      (node (ref "ENC") (pin "5") (pinfunction "WOL_5") (pintype "output"))
    )
    (net (code "82") (name "unconnected-(PJ1-GND-PadP$4)") (class "Default")
      (node (ref "PJ1") (pin "P$4") (pinfunction "GND_P$4") (pintype "bidirectional"))
    )
    (net (code "83") (name "unconnected-(U$2-PadNC)") (class "Default")
      (node (ref "U$2") (pin "NC") (pinfunction "NC_NC") (pintype "bidirectional"))
    )
    (net (code "84") (name "unconnected-(WIFI-PadRST)") (class "Default")
      (node (ref "WIFI") (pin "RST") (pinfunction "RST_RST") (pintype "bidirectional"))
    )
  )
)
